# TrafficLight.net
KiCad netlist of a schematic drawn in Altium Designer
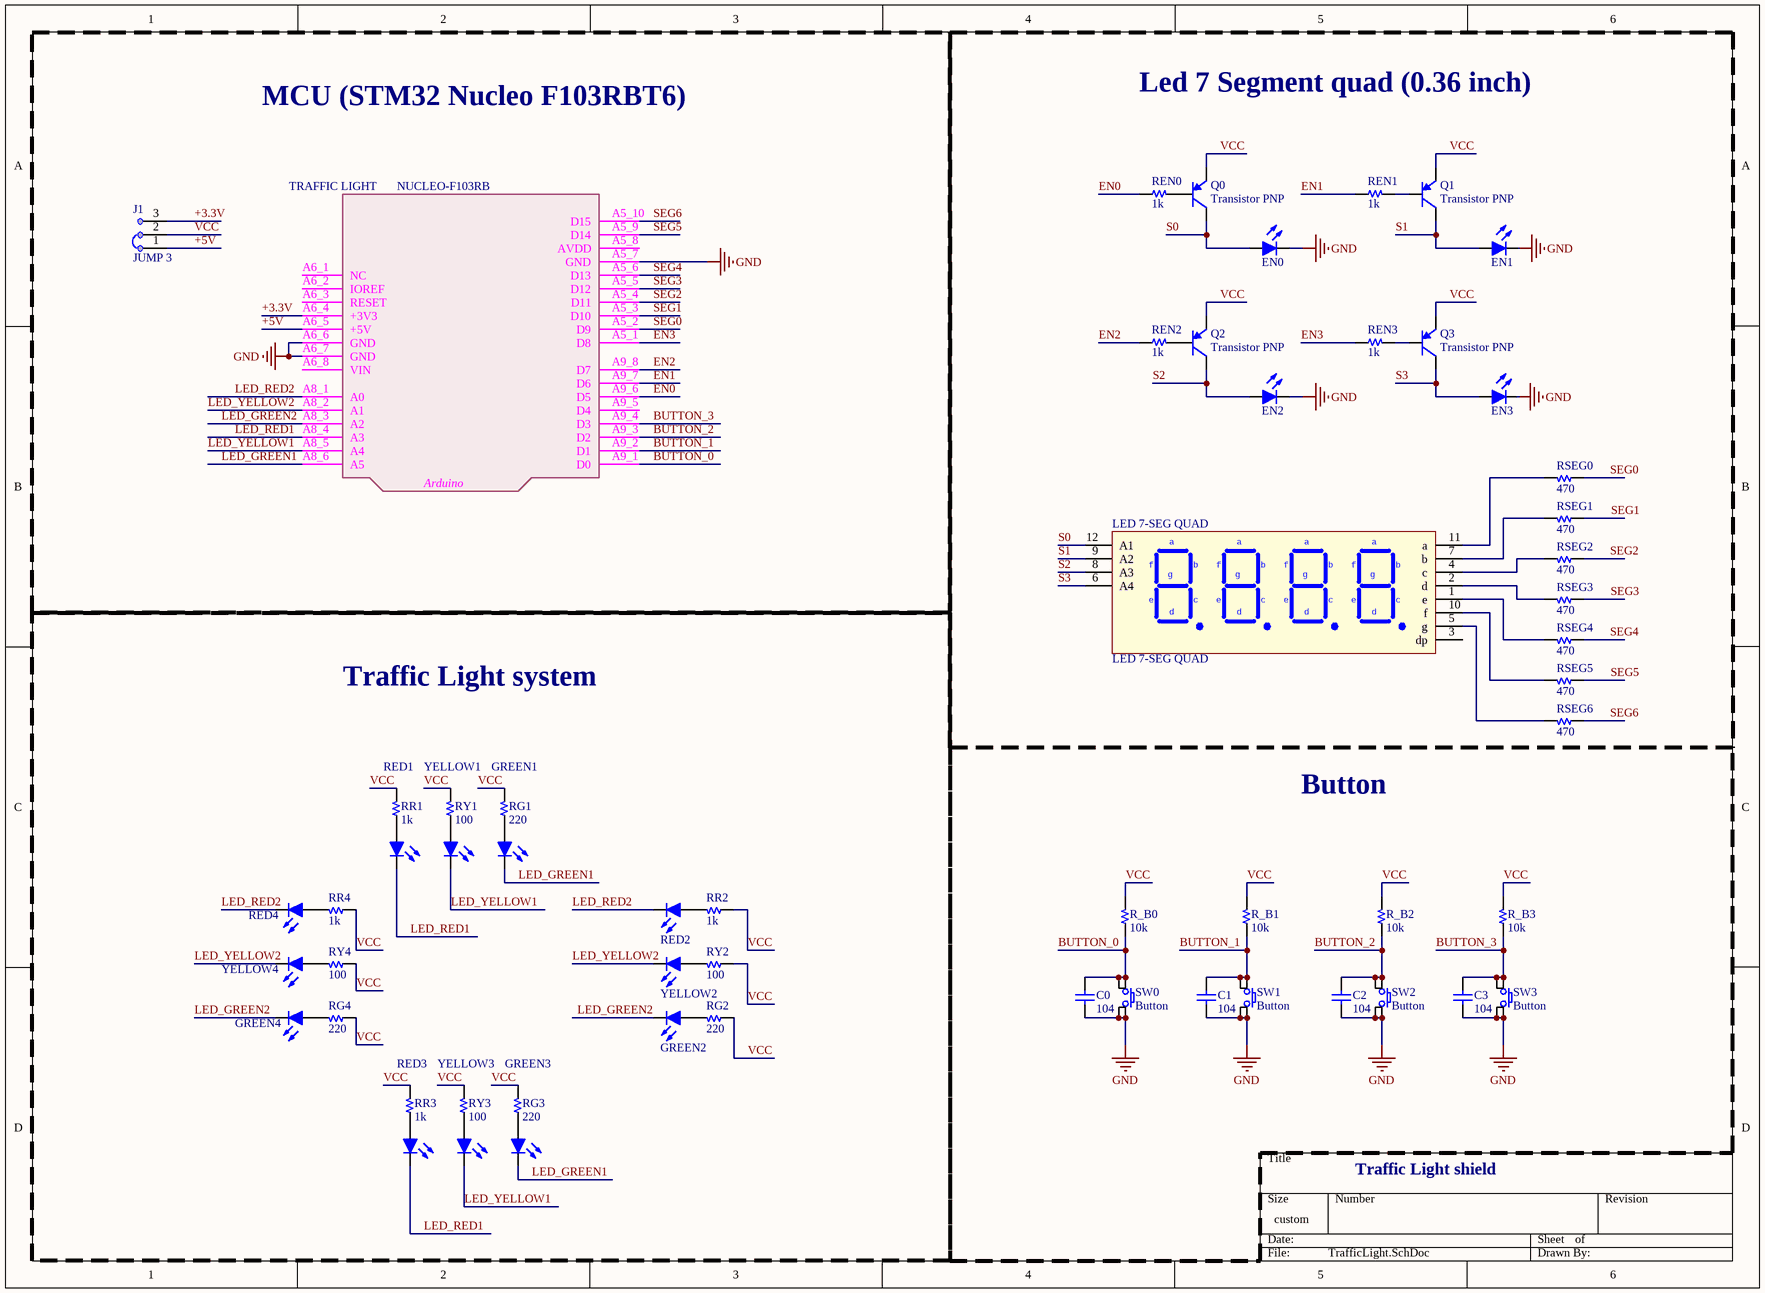
[diagram p0: TrafficLight.SchDoc]

(export (version "E")
  (design (tool "Eeschema 10.0.6"))
  (components
    (comp (ref "C0")
      (value "104")
      (footprint "C 0603")
      (description "Capacitor non-pol")
      (libsource (lib "chipfc_libs") (part "Capacitor NP"))
    )
    (comp (ref "C1")
      (value "104")
      (footprint "C 0603")
      (description "Capacitor non-pol")
      (libsource (lib "chipfc_libs") (part "Capacitor NP"))
    )
    (comp (ref "C2")
      (value "104")
      (footprint "C 0603")
      (description "Capacitor non-pol")
      (libsource (lib "chipfc_libs") (part "Capacitor NP"))
    )
    (comp (ref "C3")
      (value "104")
      (footprint "C 0603")
      (description "Capacitor non-pol")
      (libsource (lib "chipfc_libs") (part "Capacitor NP"))
    )
    (comp (ref "EN0")
      (value "Led")
      (footprint "Led 0603 - red")
      (description "Typical LED")
      (libsource (lib "led") (part "Led"))
    )
    (comp (ref "EN1")
      (value "Led")
      (footprint "Led 0603 - red")
      (description "Typical LED")
      (libsource (lib "led") (part "Led"))
    )
    (comp (ref "EN2")
      (value "Led")
      (footprint "Led 0603 - red")
      (description "Typical LED")
      (libsource (lib "led") (part "Led"))
    )
    (comp (ref "EN3")
      (value "Led")
      (footprint "Led 0603 - red")
      (description "Typical LED")
      (libsource (lib "led") (part "Led"))
    )
    (comp (ref "GREEN1")
      (value "Led")
      (footprint "LED 3MM - green")
      (description "Typical LED")
      (libsource (lib "led") (part "Led"))
    )
    (comp (ref "GREEN2")
      (value "Led")
      (footprint "LED 3MM - green")
      (description "Typical LED")
      (libsource (lib "led") (part "Led"))
    )
    (comp (ref "GREEN3")
      (value "Led")
      (footprint "LED 3MM - green")
      (description "Typical LED")
      (libsource (lib "led") (part "Led"))
    )
    (comp (ref "GREEN4")
      (value "Led")
      (footprint "LED 3MM - green")
      (description "Typical LED")
      (libsource (lib "led") (part "Led"))
    )
    (comp (ref "J1") (value "JUMP 3") (footprint "JUMP3") (libsource (lib "chipfc_libs") (part "JUMP 3")))
    (comp (ref "LED 7-SEG QUAD")
      (value "LED 7-SEG QUAD")
      (footprint "LED/7SEG/0.36/QUAD 3641")
      (description "LED 7-SEG 0.36 QUAD RED")
      (libsource (lib "led") (part "LED 7-SEG QUAD 0.36inch"))
    )
    (comp (ref "Q0")
      (value "Transistor PNP")
      (footprint "SOT-23")
      (description "PNP Bipolar Transistor")
      (libsource (lib "chipfc_libs") (part "Transistor PNP"))
    )
    (comp (ref "Q1")
      (value "Transistor PNP")
      (footprint "SOT-23")
      (description "PNP Bipolar Transistor")
      (libsource (lib "chipfc_libs") (part "Transistor PNP"))
    )
    (comp (ref "Q2")
      (value "Transistor PNP")
      (footprint "SOT-23")
      (description "PNP Bipolar Transistor")
      (libsource (lib "chipfc_libs") (part "Transistor PNP"))
    )
    (comp (ref "Q3")
      (value "Transistor PNP")
      (footprint "SOT-23")
      (description "PNP Bipolar Transistor")
      (libsource (lib "chipfc_libs") (part "Transistor PNP"))
    )
    (comp (ref "RED1")
      (value "Led")
      (footprint "LED 3MM - red")
      (description "Typical LED")
      (libsource (lib "led") (part "Led"))
    )
    (comp (ref "RED2")
      (value "Led")
      (footprint "LED 3MM - red")
      (description "Typical LED")
      (libsource (lib "led") (part "Led"))
    )
    (comp (ref "RED3")
      (value "Led")
      (footprint "LED 3MM - red")
      (description "Typical LED")
      (libsource (lib "led") (part "Led"))
    )
    (comp (ref "RED4")
      (value "Led")
      (footprint "LED 3MM - red")
      (description "Typical LED")
      (libsource (lib "led") (part "Led"))
    )
    (comp (ref "REN0")
      (value "1k")
      (footprint "R 0603")
      (description "Resistor")
      (libsource (lib "chipfc_libs") (part "Resistor"))
    )
    (comp (ref "REN1")
      (value "1k")
      (footprint "R 0603")
      (description "Resistor")
      (libsource (lib "chipfc_libs") (part "Resistor"))
    )
    (comp (ref "REN2")
      (value "1k")
      (footprint "R 0603")
      (description "Resistor")
      (libsource (lib "chipfc_libs") (part "Resistor"))
    )
    (comp (ref "REN3")
      (value "1k")
      (footprint "R 0603")
      (description "Resistor")
      (libsource (lib "chipfc_libs") (part "Resistor"))
    )
    (comp (ref "RG1")
      (value "220")
      (footprint "R 0603")
      (description "Resistor")
      (libsource (lib "chipfc_libs") (part "Resistor"))
    )
    (comp (ref "RG2")
      (value "220")
      (footprint "R 0603")
      (description "Resistor")
      (libsource (lib "chipfc_libs") (part "Resistor"))
    )
    (comp (ref "RG3")
      (value "220")
      (footprint "R 0603")
      (description "Resistor")
      (libsource (lib "chipfc_libs") (part "Resistor"))
    )
    (comp (ref "RG4")
      (value "220")
      (footprint "R 0603")
      (description "Resistor")
      (libsource (lib "chipfc_libs") (part "Resistor"))
    )
    (comp (ref "RR1")
      (value "1k")
      (footprint "R 0603")
      (description "Resistor")
      (libsource (lib "chipfc_libs") (part "Resistor"))
    )
    (comp (ref "RR2")
      (value "1k")
      (footprint "R 0603")
      (description "Resistor")
      (libsource (lib "chipfc_libs") (part "Resistor"))
    )
    (comp (ref "RR3")
      (value "1k")
      (footprint "R 0603")
      (description "Resistor")
      (libsource (lib "chipfc_libs") (part "Resistor"))
    )
    (comp (ref "RR4")
      (value "1k")
      (footprint "R 0603")
      (description "Resistor")
      (libsource (lib "chipfc_libs") (part "Resistor"))
    )
    (comp (ref "RSEG0")
      (value "470")
      (footprint "R 0603")
      (description "Resistor")
      (libsource (lib "chipfc_libs") (part "Resistor"))
    )
    (comp (ref "RSEG1")
      (value "470")
      (footprint "R 0603")
      (description "Resistor")
      (libsource (lib "chipfc_libs") (part "Resistor"))
    )
    (comp (ref "RSEG2")
      (value "470")
      (footprint "R 0603")
      (description "Resistor")
      (libsource (lib "chipfc_libs") (part "Resistor"))
    )
    (comp (ref "RSEG3")
      (value "470")
      (footprint "R 0603")
      (description "Resistor")
      (libsource (lib "chipfc_libs") (part "Resistor"))
    )
    (comp (ref "RSEG4")
      (value "470")
      (footprint "R 0603")
      (description "Resistor")
      (libsource (lib "chipfc_libs") (part "Resistor"))
    )
    (comp (ref "RSEG5")
      (value "470")
      (footprint "R 0603")
      (description "Resistor")
      (libsource (lib "chipfc_libs") (part "Resistor"))
    )
    (comp (ref "RSEG6")
      (value "470")
      (footprint "R 0603")
      (description "Resistor")
      (libsource (lib "chipfc_libs") (part "Resistor"))
    )
    (comp (ref "RY1")
      (value "100")
      (footprint "R 0603")
      (description "Resistor")
      (libsource (lib "chipfc_libs") (part "Resistor"))
    )
    (comp (ref "RY2")
      (value "100")
      (footprint "R 0603")
      (description "Resistor")
      (libsource (lib "chipfc_libs") (part "Resistor"))
    )
    (comp (ref "RY3")
      (value "100")
      (footprint "R 0603")
      (description "Resistor")
      (libsource (lib "chipfc_libs") (part "Resistor"))
    )
    (comp (ref "RY4")
      (value "100")
      (footprint "R 0603")
      (description "Resistor")
      (libsource (lib "chipfc_libs") (part "Resistor"))
    )
    (comp (ref "R_B0")
      (value "10k")
      (footprint "R 0603")
      (description "Resistor")
      (libsource (lib "chipfc_libs") (part "Resistor"))
    )
    (comp (ref "R_B1")
      (value "10k")
      (footprint "R 0603")
      (description "Resistor")
      (libsource (lib "chipfc_libs") (part "Resistor"))
    )
    (comp (ref "R_B2")
      (value "10k")
      (footprint "R 0603")
      (description "Resistor")
      (libsource (lib "chipfc_libs") (part "Resistor"))
    )
    (comp (ref "R_B3")
      (value "10k")
      (footprint "R 0603")
      (description "Resistor")
      (libsource (lib "chipfc_libs") (part "Resistor"))
    )
    (comp (ref "SW0")
      (value "Button")
      (footprint "SW/4/06MM")
      (description "Tact switch 4-pin")
      (libsource (lib "bs_libs") (part "SW SPST 4-pin"))
    )
    (comp (ref "SW1")
      (value "Button")
      (footprint "SW/4/06MM")
      (description "Tact switch 4-pin")
      (libsource (lib "bs_libs") (part "SW SPST 4-pin"))
    )
    (comp (ref "SW2")
      (value "Button")
      (footprint "SW/4/06MM")
      (description "Tact switch 4-pin")
      (libsource (lib "bs_libs") (part "SW SPST 4-pin"))
    )
    (comp (ref "SW3")
      (value "Button")
      (footprint "SW/4/06MM")
      (description "Tact switch 4-pin")
      (libsource (lib "bs_libs") (part "SW SPST 4-pin"))
    )
    (comp (ref "TRAFFIC LIGHT")
      (value "NUCLEO-F103RB")
      (footprint "NUCLEO")
      (fields (field (name "MANUFACTURER") "STMicroelectronics"))
      (libsource (lib "nucleo") (part "NUCLEO_Adruino only"))
    )
    (comp (ref "YELLOW1")
      (value "Led")
      (footprint "LED 3MM - yellow")
      (description "Typical LED")
      (libsource (lib "led") (part "Led"))
    )
    (comp (ref "YELLOW2")
      (value "Led")
      (footprint "LED 3MM - yellow")
      (description "Typical LED")
      (libsource (lib "led") (part "Led"))
    )
    (comp (ref "YELLOW3")
      (value "Led")
      (footprint "LED 3MM - yellow")
      (description "Typical LED")
      (libsource (lib "led") (part "Led"))
    )
    (comp (ref "YELLOW4")
      (value "Led")
      (footprint "LED 3MM - yellow")
      (description "Typical LED")
      (libsource (lib "led") (part "Led"))
    )
  )
  (nets
    (net (code "1") (name "/+3.3V") (class "Default")
      (node (ref "J1") (pin "3") (pinfunction "3_3") (pintype "passive"))
      (node (ref "TRAFFIC LIGHT") (pin "A6_4") (pinfunction "+3V3_A6_4") (pintype "passive"))
    )
    (net (code "2") (name "/+5V") (class "Default")
      (node (ref "J1") (pin "1") (pinfunction "1_1") (pintype "passive"))
      (node (ref "TRAFFIC LIGHT") (pin "A6_5") (pinfunction "+5V_A6_5") (pintype "passive"))
    )
    (net (code "3") (name "/BUTTON_0") (class "Default")
      (node (ref "C0") (pin "1") (pinfunction "1_1") (pintype "passive"))
      (node (ref "R_B0") (pin "1") (pinfunction "1_1") (pintype "passive"))
      (node (ref "SW0") (pin "1") (pinfunction "1_1") (pintype "passive"))
      (node (ref "SW0") (pin "2") (pinfunction "2_2") (pintype "passive"))
      (node (ref "TRAFFIC LIGHT") (pin "A9_1") (pinfunction "D0_A9_1") (pintype "passive"))
    )
    (net (code "4") (name "/BUTTON_1") (class "Default")
      (node (ref "C1") (pin "1") (pinfunction "1_1") (pintype "passive"))
      (node (ref "R_B1") (pin "1") (pinfunction "1_1") (pintype "passive"))
      (node (ref "SW1") (pin "1") (pinfunction "1_1") (pintype "passive"))
      (node (ref "SW1") (pin "2") (pinfunction "2_2") (pintype "passive"))
      (node (ref "TRAFFIC LIGHT") (pin "A9_2") (pinfunction "D1_A9_2") (pintype "passive"))
    )
    (net (code "5") (name "/BUTTON_2") (class "Default")
      (node (ref "C2") (pin "1") (pinfunction "1_1") (pintype "passive"))
      (node (ref "R_B2") (pin "1") (pinfunction "1_1") (pintype "passive"))
      (node (ref "SW2") (pin "1") (pinfunction "1_1") (pintype "passive"))
      (node (ref "SW2") (pin "2") (pinfunction "2_2") (pintype "passive"))
      (node (ref "TRAFFIC LIGHT") (pin "A9_3") (pinfunction "D2_A9_3") (pintype "passive"))
    )
    (net (code "6") (name "/BUTTON_3") (class "Default")
      (node (ref "C3") (pin "1") (pinfunction "1_1") (pintype "passive"))
      (node (ref "R_B3") (pin "1") (pinfunction "1_1") (pintype "passive"))
      (node (ref "SW3") (pin "1") (pinfunction "1_1") (pintype "passive"))
      (node (ref "SW3") (pin "2") (pinfunction "2_2") (pintype "passive"))
      (node (ref "TRAFFIC LIGHT") (pin "A9_4") (pinfunction "D3_A9_4") (pintype "passive"))
    )
    (net (code "7") (name "/EN0") (class "Default")
      (node (ref "REN0") (pin "1") (pinfunction "1_1") (pintype "passive"))
      (node (ref "TRAFFIC LIGHT") (pin "A9_6") (pinfunction "D5_A9_6") (pintype "passive"))
    )
    (net (code "8") (name "/EN1") (class "Default")
      (node (ref "REN1") (pin "1") (pinfunction "1_1") (pintype "passive"))
      (node (ref "TRAFFIC LIGHT") (pin "A9_7") (pinfunction "D6_A9_7") (pintype "passive"))
    )
    (net (code "9") (name "/EN2") (class "Default")
      (node (ref "REN2") (pin "1") (pinfunction "1_1") (pintype "passive"))
      (node (ref "TRAFFIC LIGHT") (pin "A9_8") (pinfunction "D7_A9_8") (pintype "passive"))
    )
    (net (code "10") (name "/EN3") (class "Default")
      (node (ref "REN3") (pin "1") (pinfunction "1_1") (pintype "passive"))
      (node (ref "TRAFFIC LIGHT") (pin "A5_1") (pinfunction "D8_A5_1") (pintype "passive"))
    )
    (net (code "11") (name "/LED_GREEN1") (class "Default")
      (node (ref "GREEN1") (pin "2") (pinfunction "K_2") (pintype "passive"))
      (node (ref "GREEN3") (pin "2") (pinfunction "K_2") (pintype "passive"))
      (node (ref "TRAFFIC LIGHT") (pin "A8_6") (pinfunction "A5_A8_6") (pintype "passive"))
    )
    (net (code "12") (name "/LED_GREEN2") (class "Default")
      (node (ref "GREEN2") (pin "2") (pinfunction "K_2") (pintype "passive"))
      (node (ref "GREEN4") (pin "2") (pinfunction "K_2") (pintype "passive"))
      (node (ref "TRAFFIC LIGHT") (pin "A8_3") (pinfunction "A2_A8_3") (pintype "passive"))
    )
    (net (code "13") (name "/LED_RED1") (class "Default")
      (node (ref "RED1") (pin "2") (pinfunction "K_2") (pintype "passive"))
      (node (ref "RED3") (pin "2") (pinfunction "K_2") (pintype "passive"))
      (node (ref "TRAFFIC LIGHT") (pin "A8_4") (pinfunction "A3_A8_4") (pintype "passive"))
    )
    (net (code "14") (name "/LED_RED2") (class "Default")
      (node (ref "RED2") (pin "2") (pinfunction "K_2") (pintype "passive"))
      (node (ref "RED4") (pin "2") (pinfunction "K_2") (pintype "passive"))
      (node (ref "TRAFFIC LIGHT") (pin "A8_1") (pinfunction "A0_A8_1") (pintype "passive"))
    )
    (net (code "15") (name "/LED_YELLOW1") (class "Default")
      (node (ref "TRAFFIC LIGHT") (pin "A8_5") (pinfunction "A4_A8_5") (pintype "passive"))
      (node (ref "YELLOW1") (pin "2") (pinfunction "K_2") (pintype "passive"))
      (node (ref "YELLOW3") (pin "2") (pinfunction "K_2") (pintype "passive"))
    )
    (net (code "16") (name "/LED_YELLOW2") (class "Default")
      (node (ref "TRAFFIC LIGHT") (pin "A8_2") (pinfunction "A1_A8_2") (pintype "passive"))
      (node (ref "YELLOW2") (pin "2") (pinfunction "K_2") (pintype "passive"))
      (node (ref "YELLOW4") (pin "2") (pinfunction "K_2") (pintype "passive"))
    )
    (net (code "17") (name "/S0") (class "Default")
      (node (ref "EN0") (pin "1") (pinfunction "A_1") (pintype "passive"))
      (node (ref "LED 7-SEG QUAD") (pin "12") (pinfunction "A1_12") (pintype "passive"))
      (node (ref "Q0") (pin "3") (pinfunction "C_3") (pintype "passive"))
    )
    (net (code "18") (name "/S1") (class "Default")
      (node (ref "EN1") (pin "1") (pinfunction "A_1") (pintype "passive"))
      (node (ref "LED 7-SEG QUAD") (pin "9") (pinfunction "A2_9") (pintype "passive"))
      (node (ref "Q1") (pin "3") (pinfunction "C_3") (pintype "passive"))
    )
    (net (code "19") (name "/S2") (class "Default")
      (node (ref "EN2") (pin "1") (pinfunction "A_1") (pintype "passive"))
      (node (ref "LED 7-SEG QUAD") (pin "8") (pinfunction "A3_8") (pintype "passive"))
      (node (ref "Q2") (pin "3") (pinfunction "C_3") (pintype "passive"))
    )
    (net (code "20") (name "/S3") (class "Default")
      (node (ref "EN3") (pin "1") (pinfunction "A_1") (pintype "passive"))
      (node (ref "LED 7-SEG QUAD") (pin "6") (pinfunction "A4_6") (pintype "passive"))
      (node (ref "Q3") (pin "3") (pinfunction "C_3") (pintype "passive"))
    )
    (net (code "21") (name "/SEG0") (class "Default")
      (node (ref "RSEG0") (pin "1") (pinfunction "1_1") (pintype "passive"))
      (node (ref "TRAFFIC LIGHT") (pin "A5_2") (pinfunction "D9_A5_2") (pintype "passive"))
    )
    (net (code "22") (name "/SEG1") (class "Default")
      (node (ref "RSEG1") (pin "1") (pinfunction "1_1") (pintype "passive"))
      (node (ref "TRAFFIC LIGHT") (pin "A5_3") (pinfunction "D10_A5_3") (pintype "passive"))
    )
    (net (code "23") (name "/SEG2") (class "Default")
      (node (ref "RSEG2") (pin "1") (pinfunction "1_1") (pintype "passive"))
      (node (ref "TRAFFIC LIGHT") (pin "A5_4") (pinfunction "D11_A5_4") (pintype "passive"))
    )
    (net (code "24") (name "/SEG3") (class "Default")
      (node (ref "RSEG3") (pin "1") (pinfunction "1_1") (pintype "passive"))
      (node (ref "TRAFFIC LIGHT") (pin "A5_5") (pinfunction "D12_A5_5") (pintype "passive"))
    )
    (net (code "25") (name "/SEG4") (class "Default")
      (node (ref "RSEG4") (pin "1") (pinfunction "1_1") (pintype "passive"))
      (node (ref "TRAFFIC LIGHT") (pin "A5_6") (pinfunction "D13_A5_6") (pintype "passive"))
    )
    (net (code "26") (name "/SEG5") (class "Default")
      (node (ref "RSEG5") (pin "1") (pinfunction "1_1") (pintype "passive"))
      (node (ref "TRAFFIC LIGHT") (pin "A5_9") (pinfunction "D14_A5_9") (pintype "passive"))
    )
    (net (code "27") (name "/SEG6") (class "Default")
      (node (ref "RSEG6") (pin "1") (pinfunction "1_1") (pintype "passive"))
      (node (ref "TRAFFIC LIGHT") (pin "A5_10") (pinfunction "D15_A5_10") (pintype "passive"))
    )
    (net (code "28") (name "/VCC") (class "Default")
      (node (ref "J1") (pin "2") (pinfunction "2_2") (pintype "passive"))
      (node (ref "Q0") (pin "2") (pinfunction "E_2") (pintype "passive"))
      (node (ref "Q1") (pin "2") (pinfunction "E_2") (pintype "passive"))
      (node (ref "Q2") (pin "2") (pinfunction "E_2") (pintype "passive"))
      (node (ref "Q3") (pin "2") (pinfunction "E_2") (pintype "passive"))
      (node (ref "RG1") (pin "2") (pinfunction "2_2") (pintype "passive"))
      (node (ref "RG2") (pin "1") (pinfunction "1_1") (pintype "passive"))
      (node (ref "RG3") (pin "2") (pinfunction "2_2") (pintype "passive"))
      (node (ref "RG4") (pin "1") (pinfunction "1_1") (pintype "passive"))
      (node (ref "RR1") (pin "2") (pinfunction "2_2") (pintype "passive"))
      (node (ref "RR2") (pin "1") (pinfunction "1_1") (pintype "passive"))
      (node (ref "RR3") (pin "2") (pinfunction "2_2") (pintype "passive"))
      (node (ref "RR4") (pin "1") (pinfunction "1_1") (pintype "passive"))
      (node (ref "RY1") (pin "2") (pinfunction "2_2") (pintype "passive"))
      (node (ref "RY2") (pin "1") (pinfunction "1_1") (pintype "passive"))
      (node (ref "RY3") (pin "2") (pinfunction "2_2") (pintype "passive"))
      (node (ref "RY4") (pin "1") (pinfunction "1_1") (pintype "passive"))
      (node (ref "R_B0") (pin "2") (pinfunction "2_2") (pintype "passive"))
      (node (ref "R_B1") (pin "2") (pinfunction "2_2") (pintype "passive"))
      (node (ref "R_B2") (pin "2") (pinfunction "2_2") (pintype "passive"))
      (node (ref "R_B3") (pin "2") (pinfunction "2_2") (pintype "passive"))
    )
    (net (code "29") (name "GND") (class "Default")
      (node (ref "C0") (pin "2") (pinfunction "2_2") (pintype "passive"))
      (node (ref "C1") (pin "2") (pinfunction "2_2") (pintype "passive"))
      (node (ref "C2") (pin "2") (pinfunction "2_2") (pintype "passive"))
      (node (ref "C3") (pin "2") (pinfunction "2_2") (pintype "passive"))
      (node (ref "EN0") (pin "2") (pinfunction "K_2") (pintype "passive"))
      (node (ref "EN1") (pin "2") (pinfunction "K_2") (pintype "passive"))
      (node (ref "EN2") (pin "2") (pinfunction "K_2") (pintype "passive"))
      (node (ref "EN3") (pin "2") (pinfunction "K_2") (pintype "passive"))
      (node (ref "SW0") (pin "3") (pinfunction "3_3") (pintype "passive"))
      (node (ref "SW0") (pin "4") (pinfunction "4_4") (pintype "passive"))
      (node (ref "SW1") (pin "3") (pinfunction "3_3") (pintype "passive"))
      (node (ref "SW1") (pin "4") (pinfunction "4_4") (pintype "passive"))
      (node (ref "SW2") (pin "3") (pinfunction "3_3") (pintype "passive"))
      (node (ref "SW2") (pin "4") (pinfunction "4_4") (pintype "passive"))
      (node (ref "SW3") (pin "3") (pinfunction "3_3") (pintype "passive"))
      (node (ref "SW3") (pin "4") (pinfunction "4_4") (pintype "passive"))
      (node (ref "TRAFFIC LIGHT") (pin "A5_7") (pinfunction "GND_A5_7") (pintype "passive"))
      (node (ref "TRAFFIC LIGHT") (pin "A6_6") (pinfunction "GND_A6_6") (pintype "passive"))
      (node (ref "TRAFFIC LIGHT") (pin "A6_7") (pinfunction "GND_A6_7") (pintype "passive"))
    )
    (net (code "30") (name "Net-(GREEN1-A)") (class "Default")
      (node (ref "GREEN1") (pin "1") (pinfunction "A_1") (pintype "passive"))
      (node (ref "RG1") (pin "1") (pinfunction "1_1") (pintype "passive"))
    )
    (net (code "31") (name "Net-(GREEN2-A)") (class "Default")
      (node (ref "GREEN2") (pin "1") (pinfunction "A_1") (pintype "passive"))
      (node (ref "RG2") (pin "2") (pinfunction "2_2") (pintype "passive"))
    )
    (net (code "32") (name "Net-(GREEN3-A)") (class "Default")
      (node (ref "GREEN3") (pin "1") (pinfunction "A_1") (pintype "passive"))
      (node (ref "RG3") (pin "1") (pinfunction "1_1") (pintype "passive"))
    )
    (net (code "33") (name "Net-(GREEN4-A)") (class "Default")
      (node (ref "GREEN4") (pin "1") (pinfunction "A_1") (pintype "passive"))
      (node (ref "RG4") (pin "2") (pinfunction "2_2") (pintype "passive"))
    )
    (net (code "34") (name "Net-(LED 7-SEG QUAD-a)") (class "Default")
      (node (ref "LED 7-SEG QUAD") (pin "11") (pinfunction "a_11") (pintype "passive"))
      (node (ref "RSEG0") (pin "2") (pinfunction "2_2") (pintype "passive"))
    )
    (net (code "35") (name "Net-(LED 7-SEG QUAD-b)") (class "Default")
      (node (ref "LED 7-SEG QUAD") (pin "7") (pinfunction "b_7") (pintype "passive"))
      (node (ref "RSEG1") (pin "2") (pinfunction "2_2") (pintype "passive"))
    )
    (net (code "36") (name "Net-(LED 7-SEG QUAD-c)") (class "Default")
      (node (ref "LED 7-SEG QUAD") (pin "4") (pinfunction "c_4") (pintype "passive"))
      (node (ref "RSEG2") (pin "2") (pinfunction "2_2") (pintype "passive"))
    )
    (net (code "37") (name "Net-(LED 7-SEG QUAD-d)") (class "Default")
      (node (ref "LED 7-SEG QUAD") (pin "2") (pinfunction "d_2") (pintype "passive"))
      (node (ref "RSEG3") (pin "2") (pinfunction "2_2") (pintype "passive"))
    )
    (net (code "38") (name "Net-(LED 7-SEG QUAD-e)") (class "Default")
      (node (ref "LED 7-SEG QUAD") (pin "1") (pinfunction "e_1") (pintype "passive"))
      (node (ref "RSEG4") (pin "2") (pinfunction "2_2") (pintype "passive"))
    )
    (net (code "39") (name "Net-(LED 7-SEG QUAD-f)") (class "Default")
      (node (ref "LED 7-SEG QUAD") (pin "10") (pinfunction "f_10") (pintype "passive"))
      (node (ref "RSEG5") (pin "2") (pinfunction "2_2") (pintype "passive"))
    )
    (net (code "40") (name "Net-(LED 7-SEG QUAD-g)") (class "Default")
      (node (ref "LED 7-SEG QUAD") (pin "5") (pinfunction "g_5") (pintype "passive"))
      (node (ref "RSEG6") (pin "2") (pinfunction "2_2") (pintype "passive"))
    )
    (net (code "41") (name "Net-(Q0-B)") (class "Default")
      (node (ref "Q0") (pin "1") (pinfunction "B_1") (pintype "passive"))
      (node (ref "REN0") (pin "2") (pinfunction "2_2") (pintype "passive"))
    )
    (net (code "42") (name "Net-(Q1-B)") (class "Default")
      (node (ref "Q1") (pin "1") (pinfunction "B_1") (pintype "passive"))
      (node (ref "REN1") (pin "2") (pinfunction "2_2") (pintype "passive"))
    )
    (net (code "43") (name "Net-(Q2-B)") (class "Default")
      (node (ref "Q2") (pin "1") (pinfunction "B_1") (pintype "passive"))
      (node (ref "REN2") (pin "2") (pinfunction "2_2") (pintype "passive"))
    )
    (net (code "44") (name "Net-(Q3-B)") (class "Default")
      (node (ref "Q3") (pin "1") (pinfunction "B_1") (pintype "passive"))
      (node (ref "REN3") (pin "2") (pinfunction "2_2") (pintype "passive"))
    )
    (net (code "45") (name "Net-(RED1-A)") (class "Default")
      (node (ref "RED1") (pin "1") (pinfunction "A_1") (pintype "passive"))
      (node (ref "RR1") (pin "1") (pinfunction "1_1") (pintype "passive"))
    )
    (net (code "46") (name "Net-(RED2-A)") (class "Default")
      (node (ref "RED2") (pin "1") (pinfunction "A_1") (pintype "passive"))
      (node (ref "RR2") (pin "2") (pinfunction "2_2") (pintype "passive"))
    )
    (net (code "47") (name "Net-(RED3-A)") (class "Default")
      (node (ref "RED3") (pin "1") (pinfunction "A_1") (pintype "passive"))
      (node (ref "RR3") (pin "1") (pinfunction "1_1") (pintype "passive"))
    )
    (net (code "48") (name "Net-(RED4-A)") (class "Default")
      (node (ref "RED4") (pin "1") (pinfunction "A_1") (pintype "passive"))
      (node (ref "RR4") (pin "2") (pinfunction "2_2") (pintype "passive"))
    )
    (net (code "49") (name "Net-(YELLOW1-A)") (class "Default")
      (node (ref "RY1") (pin "1") (pinfunction "1_1") (pintype "passive"))
      (node (ref "YELLOW1") (pin "1") (pinfunction "A_1") (pintype "passive"))
    )
    (net (code "50") (name "Net-(YELLOW2-A)") (class "Default")
      (node (ref "RY2") (pin "2") (pinfunction "2_2") (pintype "passive"))
      (node (ref "YELLOW2") (pin "1") (pinfunction "A_1") (pintype "passive"))
    )
    (net (code "51") (name "Net-(YELLOW3-A)") (class "Default")
      (node (ref "RY3") (pin "1") (pinfunction "1_1") (pintype "passive"))
      (node (ref "YELLOW3") (pin "1") (pinfunction "A_1") (pintype "passive"))
    )
    (net (code "52") (name "Net-(YELLOW4-A)") (class "Default")
      (node (ref "RY4") (pin "2") (pinfunction "2_2") (pintype "passive"))
      (node (ref "YELLOW4") (pin "1") (pinfunction "A_1") (pintype "passive"))
    )
    (net (code "53") (name "unconnected-(LED 7-SEG QUAD-dp-Pad3)") (class "Default")
      (node (ref "LED 7-SEG QUAD") (pin "3") (pinfunction "dp_3") (pintype "passive"))
    )
    (net (code "54") (name "unconnected-(TRAFFIC LIGHT-AVDD-PadA5_8)") (class "Default")
      (node (ref "TRAFFIC LIGHT") (pin "A5_8") (pinfunction "AVDD_A5_8") (pintype "passive"))
    )
    (net (code "55") (name "unconnected-(TRAFFIC LIGHT-D4-PadA9_5)") (class "Default")
      (node (ref "TRAFFIC LIGHT") (pin "A9_5") (pinfunction "D4_A9_5") (pintype "passive"))
    )
    (net (code "56") (name "unconnected-(TRAFFIC LIGHT-IOREF-PadA6_2)") (class "Default")
      (node (ref "TRAFFIC LIGHT") (pin "A6_2") (pinfunction "IOREF_A6_2") (pintype "passive"))
    )
    (net (code "57") (name "unconnected-(TRAFFIC LIGHT-NC-PadA6_1)") (class "Default")
      (node (ref "TRAFFIC LIGHT") (pin "A6_1") (pinfunction "NC_A6_1") (pintype "passive"))
    )
    (net (code "58") (name "unconnected-(TRAFFIC LIGHT-RESET-PadA6_3)") (class "Default")
      (node (ref "TRAFFIC LIGHT") (pin "A6_3") (pinfunction "RESET_A6_3") (pintype "passive"))
    )
    (net (code "59") (name "unconnected-(TRAFFIC LIGHT-VIN-PadA6_8)") (class "Default")
      (node (ref "TRAFFIC LIGHT") (pin "A6_8") (pinfunction "VIN_A6_8") (pintype "passive"))
    )
  )
)
